# M149A.net
KiCad netlist of a schematic drawn in EAGLE
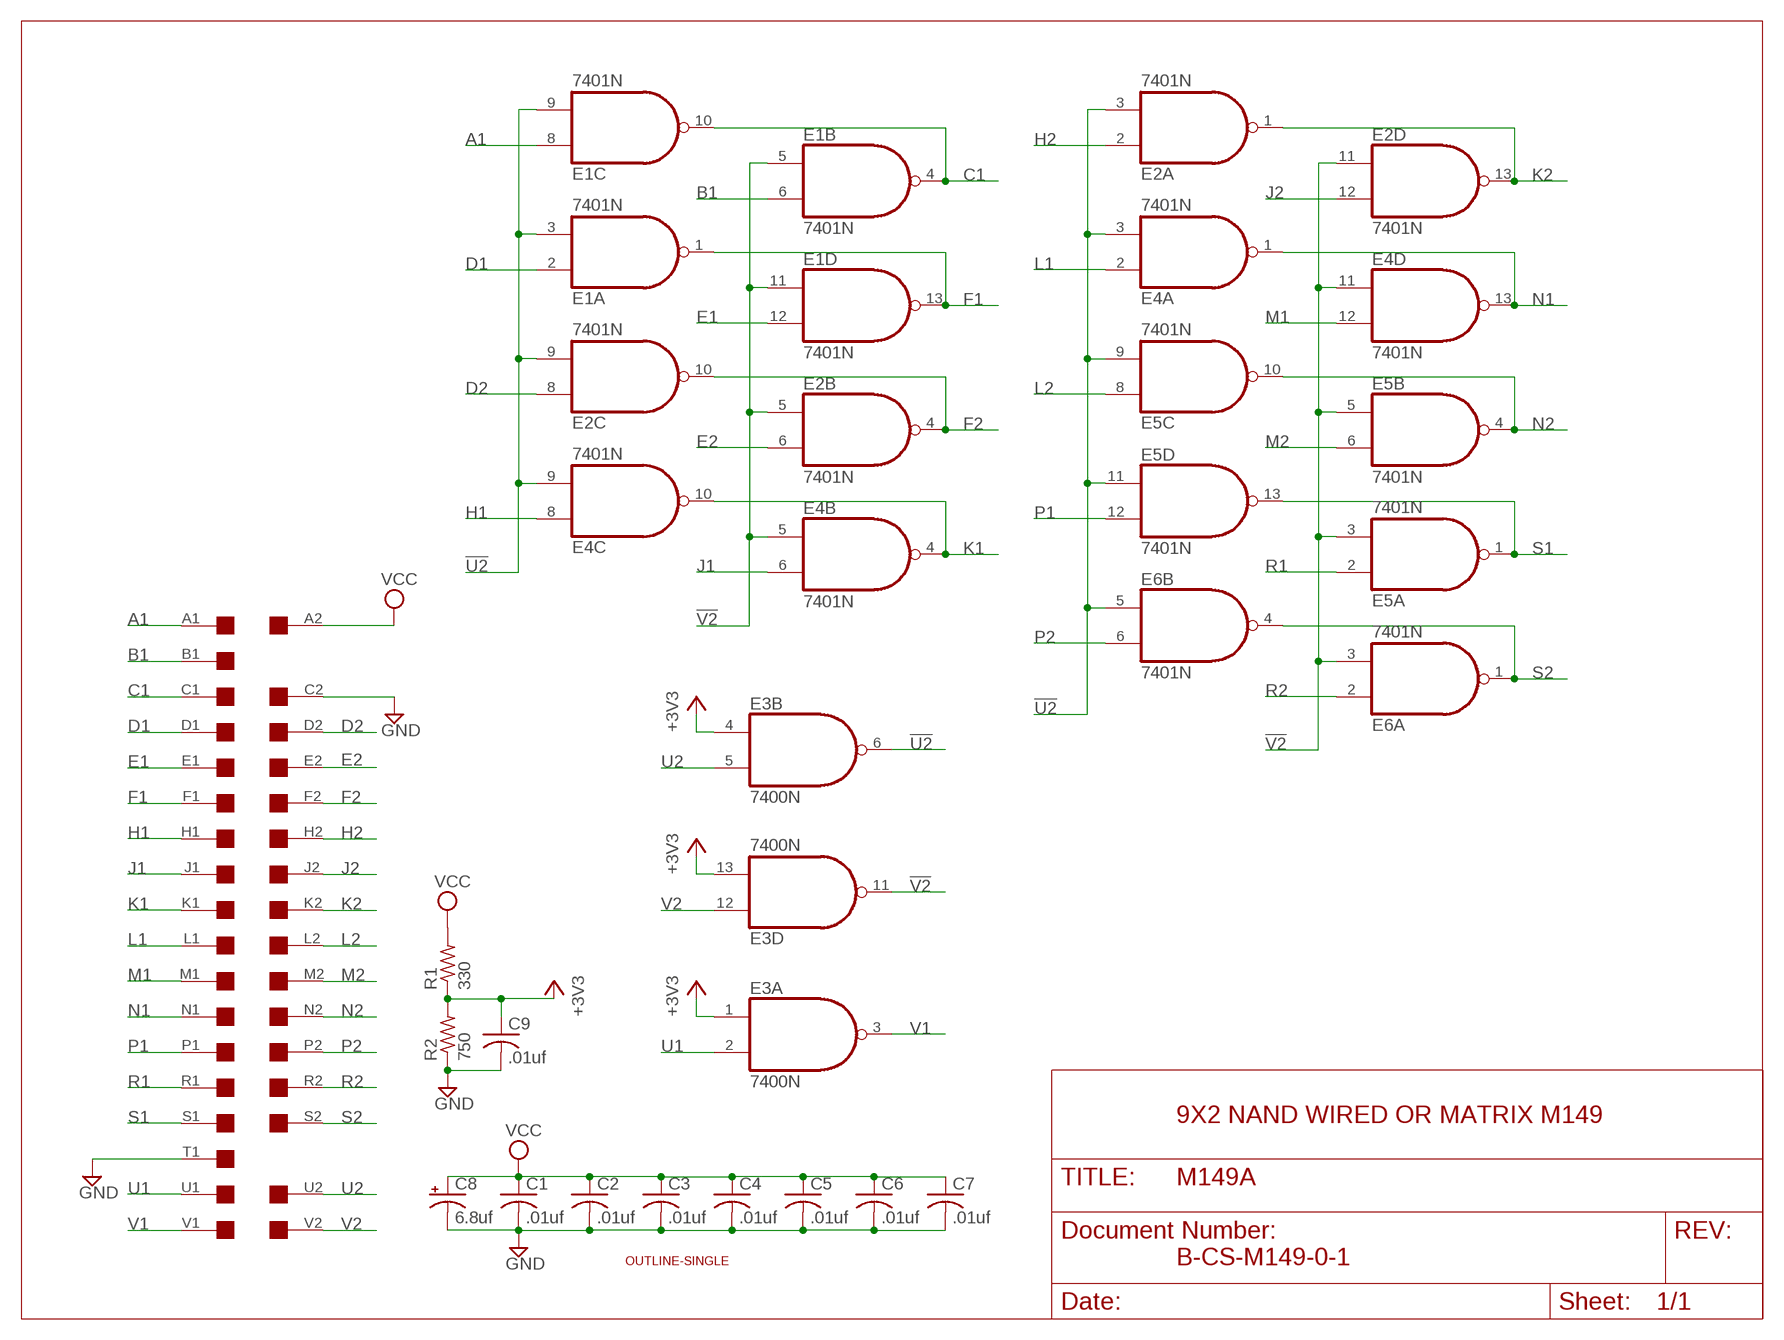
[diagram p0: schematic, sheet 1]

(export (version "E")
  (design (tool "Eeschema 10.0.6"))
  (components
    (comp (ref "C1")
      (value ".01uf")
      (footprint "eagle-import:C050-025X075")
      (libsource (lib "eagle-import") (part "C-US050-025X075"))
    )
    (comp (ref "C2")
      (value ".01uf")
      (footprint "eagle-import:C050-025X075")
      (libsource (lib "eagle-import") (part "C-US050-025X075"))
    )
    (comp (ref "C3")
      (value ".01uf")
      (footprint "eagle-import:C050-025X075")
      (libsource (lib "eagle-import") (part "C-US050-025X075"))
    )
    (comp (ref "C4")
      (value ".01uf")
      (footprint "eagle-import:C050-025X075")
      (libsource (lib "eagle-import") (part "C-US050-025X075"))
    )
    (comp (ref "C5")
      (value ".01uf")
      (footprint "eagle-import:C050-025X075")
      (libsource (lib "eagle-import") (part "C-US050-025X075"))
    )
    (comp (ref "C6")
      (value ".01uf")
      (footprint "eagle-import:C050-025X075")
      (libsource (lib "eagle-import") (part "C-US050-025X075"))
    )
    (comp (ref "C7")
      (value ".01uf")
      (footprint "eagle-import:C050-025X075")
      (libsource (lib "eagle-import") (part "C-US050-025X075"))
    )
    (comp (ref "C8")
      (value "6.8uf")
      (footprint "eagle-import:E15-5")
      (libsource (lib "eagle-import") (part "CPOL-USE15-5AXIAL"))
    )
    (comp (ref "C9")
      (value ".01uf")
      (footprint "eagle-import:C050-025X075")
      (libsource (lib "eagle-import") (part "C-US050-025X075"))
    )
    (comp (ref "E1")
      (value "7401N")
      (footprint "eagle-import:DIL14")
      (libsource (lib "eagle-import") (part "7401NLS"))
    )
    (comp (ref "E2")
      (value "7401N")
      (footprint "eagle-import:DIL14")
      (libsource (lib "eagle-import") (part "7401NLS"))
    )
    (comp (ref "E3")
      (value "7400N")
      (footprint "eagle-import:DIL14")
      (libsource (lib "eagle-import") (part "7400N"))
    )
    (comp (ref "E4")
      (value "7401N")
      (footprint "eagle-import:DIL14")
      (libsource (lib "eagle-import") (part "7401NLS"))
    )
    (comp (ref "E5")
      (value "7401N")
      (footprint "eagle-import:DIL14")
      (libsource (lib "eagle-import") (part "7401NLS"))
    )
    (comp (ref "E6")
      (value "7401N")
      (footprint "eagle-import:DIL14")
      (libsource (lib "eagle-import") (part "7401NLS"))
    )
    (comp (ref "R1")
      (value "330")
      (footprint "eagle-import:0207_10")
      (libsource (lib "eagle-import") (part "R-US_0207/10"))
    )
    (comp (ref "R2")
      (value "750")
      (footprint "eagle-import:0207_10")
      (libsource (lib "eagle-import") (part "R-US_0207/10"))
    )
    (comp (ref "U$1")
      (value "SINGLE")
      (footprint "eagle-import:EDGE-CON2")
      (libsource (lib "eagle-import") (part "SINGLE"))
    )
    (comp (ref "U$4")
      (value "OUTLINE-SINGLE")
      (footprint "eagle-import:SINGLE")
      (libsource (lib "eagle-import") (part "OUTLINE-SINGLE"))
    )
  )
  (nets
    (net (code "1") (name "+3V3") (class "Default")
      (node (ref "C9") (pin "1") (pinfunction "1_1") (pintype "passive"))
      (node (ref "E3") (pin "1") (pinfunction "I0_1") (pintype "input"))
      (node (ref "E3") (pin "13") (pinfunction "I1_13") (pintype "input"))
      (node (ref "E3") (pin "4") (pinfunction "I0_4") (pintype "input"))
      (node (ref "R1") (pin "1") (pinfunction "1_1") (pintype "passive"))
      (node (ref "R2") (pin "2") (pinfunction "2_2") (pintype "passive"))
    )
    (net (code "2") (name "/A1") (class "Default")
      (node (ref "E1") (pin "8") (pinfunction "I0_8") (pintype "input"))
      (node (ref "U$1") (pin "A1") (pinfunction "1_A1") (pintype "bidirectional"))
    )
    (net (code "3") (name "/B1") (class "Default")
      (node (ref "E1") (pin "6") (pinfunction "I1_6") (pintype "input"))
      (node (ref "U$1") (pin "B1") (pinfunction "1_B1") (pintype "bidirectional"))
    )
    (net (code "4") (name "/C1") (class "Default")
      (node (ref "E1") (pin "10") (pinfunction "O_10") (pintype "open_collector"))
      (node (ref "E1") (pin "4") (pinfunction "O_4") (pintype "open_collector"))
      (node (ref "U$1") (pin "C1") (pinfunction "1_C1") (pintype "bidirectional"))
    )
    (net (code "5") (name "/D1") (class "Default")
      (node (ref "E1") (pin "2") (pinfunction "I0_2") (pintype "input"))
      (node (ref "U$1") (pin "D1") (pinfunction "1_D1") (pintype "bidirectional"))
    )
    (net (code "6") (name "/D2") (class "Default")
      (node (ref "E2") (pin "8") (pinfunction "I0_8") (pintype "input"))
      (node (ref "U$1") (pin "D2") (pinfunction "1_D2") (pintype "bidirectional"))
    )
    (net (code "7") (name "/E1") (class "Default")
      (node (ref "E1") (pin "12") (pinfunction "I1_12") (pintype "input"))
      (node (ref "U$1") (pin "E1") (pinfunction "1_E1") (pintype "bidirectional"))
    )
    (net (code "8") (name "/E2") (class "Default")
      (node (ref "E2") (pin "6") (pinfunction "I1_6") (pintype "input"))
      (node (ref "U$1") (pin "E2") (pinfunction "1_E2") (pintype "bidirectional"))
    )
    (net (code "9") (name "/F1") (class "Default")
      (node (ref "E1") (pin "1") (pinfunction "O_1") (pintype "open_collector"))
      (node (ref "E1") (pin "13") (pinfunction "O_13") (pintype "open_collector"))
      (node (ref "U$1") (pin "F1") (pinfunction "1_F1") (pintype "bidirectional"))
    )
    (net (code "10") (name "/F2") (class "Default")
      (node (ref "E2") (pin "10") (pinfunction "O_10") (pintype "open_collector"))
      (node (ref "E2") (pin "4") (pinfunction "O_4") (pintype "open_collector"))
      (node (ref "U$1") (pin "F2") (pinfunction "1_F2") (pintype "bidirectional"))
    )
    (net (code "11") (name "/H1") (class "Default")
      (node (ref "E4") (pin "8") (pinfunction "I0_8") (pintype "input"))
      (node (ref "U$1") (pin "H1") (pinfunction "1_H1") (pintype "bidirectional"))
    )
    (net (code "12") (name "/H2") (class "Default")
      (node (ref "E2") (pin "2") (pinfunction "I0_2") (pintype "input"))
      (node (ref "U$1") (pin "H2") (pinfunction "1_H2") (pintype "bidirectional"))
    )
    (net (code "13") (name "/J1") (class "Default")
      (node (ref "E4") (pin "6") (pinfunction "I1_6") (pintype "input"))
      (node (ref "U$1") (pin "J1") (pinfunction "1_J1") (pintype "bidirectional"))
    )
    (net (code "14") (name "/J2") (class "Default")
      (node (ref "E2") (pin "12") (pinfunction "I1_12") (pintype "input"))
      (node (ref "U$1") (pin "J2") (pinfunction "1_J2") (pintype "bidirectional"))
    )
    (net (code "15") (name "/K1") (class "Default")
      (node (ref "E4") (pin "10") (pinfunction "O_10") (pintype "open_collector"))
      (node (ref "E4") (pin "4") (pinfunction "O_4") (pintype "open_collector"))
      (node (ref "U$1") (pin "K1") (pinfunction "1_K1") (pintype "bidirectional"))
    )
    (net (code "16") (name "/K2") (class "Default")
      (node (ref "E2") (pin "1") (pinfunction "O_1") (pintype "open_collector"))
      (node (ref "E2") (pin "13") (pinfunction "O_13") (pintype "open_collector"))
      (node (ref "U$1") (pin "K2") (pinfunction "1_K2") (pintype "bidirectional"))
    )
    (net (code "17") (name "/L1") (class "Default")
      (node (ref "E4") (pin "2") (pinfunction "I0_2") (pintype "input"))
      (node (ref "U$1") (pin "L1") (pinfunction "1_L1") (pintype "bidirectional"))
    )
    (net (code "18") (name "/L2") (class "Default")
      (node (ref "E5") (pin "8") (pinfunction "I0_8") (pintype "input"))
      (node (ref "U$1") (pin "L2") (pinfunction "1_L2") (pintype "bidirectional"))
    )
    (net (code "19") (name "/M1") (class "Default")
      (node (ref "E4") (pin "12") (pinfunction "I1_12") (pintype "input"))
      (node (ref "U$1") (pin "M1") (pinfunction "1_M1") (pintype "bidirectional"))
    )
    (net (code "20") (name "/M2") (class "Default")
      (node (ref "E5") (pin "6") (pinfunction "I1_6") (pintype "input"))
      (node (ref "U$1") (pin "M2") (pinfunction "1_M2") (pintype "bidirectional"))
    )
    (net (code "21") (name "/N1") (class "Default")
      (node (ref "E4") (pin "1") (pinfunction "O_1") (pintype "open_collector"))
      (node (ref "E4") (pin "13") (pinfunction "O_13") (pintype "open_collector"))
      (node (ref "U$1") (pin "N1") (pinfunction "1_N1") (pintype "bidirectional"))
    )
    (net (code "22") (name "/N2") (class "Default")
      (node (ref "E5") (pin "10") (pinfunction "O_10") (pintype "open_collector"))
      (node (ref "E5") (pin "4") (pinfunction "O_4") (pintype "open_collector"))
      (node (ref "U$1") (pin "N2") (pinfunction "1_N2") (pintype "bidirectional"))
    )
    (net (code "23") (name "/P1") (class "Default")
      (node (ref "E5") (pin "12") (pinfunction "I1_12") (pintype "input"))
      (node (ref "U$1") (pin "P1") (pinfunction "1_P1") (pintype "bidirectional"))
    )
    (net (code "24") (name "/P2") (class "Default")
      (node (ref "E6") (pin "6") (pinfunction "I1_6") (pintype "input"))
      (node (ref "U$1") (pin "P2") (pinfunction "1_P2") (pintype "bidirectional"))
    )
    (net (code "25") (name "/R1") (class "Default")
      (node (ref "E5") (pin "2") (pinfunction "I0_2") (pintype "input"))
      (node (ref "U$1") (pin "R1") (pinfunction "1_R1") (pintype "bidirectional"))
    )
    (net (code "26") (name "/R2") (class "Default")
      (node (ref "E6") (pin "2") (pinfunction "I0_2") (pintype "input"))
      (node (ref "U$1") (pin "R2") (pinfunction "1_R2") (pintype "bidirectional"))
    )
    (net (code "27") (name "/S1") (class "Default")
      (node (ref "E5") (pin "1") (pinfunction "O_1") (pintype "open_collector"))
      (node (ref "E5") (pin "13") (pinfunction "O_13") (pintype "open_collector"))
      (node (ref "U$1") (pin "S1") (pinfunction "1_S1") (pintype "bidirectional"))
    )
    (net (code "28") (name "/S2") (class "Default")
      (node (ref "E6") (pin "1") (pinfunction "O_1") (pintype "open_collector"))
      (node (ref "E6") (pin "4") (pinfunction "O_4") (pintype "open_collector"))
      (node (ref "U$1") (pin "S2") (pinfunction "1_S2") (pintype "bidirectional"))
    )
    (net (code "29") (name "/U1") (class "Default")
      (node (ref "E3") (pin "2") (pinfunction "I1_2") (pintype "input"))
      (node (ref "U$1") (pin "U1") (pinfunction "1_U1") (pintype "bidirectional"))
    )
    (net (code "30") (name "/U2") (class "Default")
      (node (ref "E3") (pin "5") (pinfunction "I1_5") (pintype "input"))
      (node (ref "U$1") (pin "U2") (pinfunction "1_U2") (pintype "bidirectional"))
    )
    (net (code "31") (name "/V1") (class "Default")
      (node (ref "E3") (pin "3") (pinfunction "O_3") (pintype "output"))
      (node (ref "U$1") (pin "V1") (pinfunction "1_V1") (pintype "bidirectional"))
    )
    (net (code "32") (name "/V2") (class "Default")
      (node (ref "E3") (pin "12") (pinfunction "I0_12") (pintype "input"))
      (node (ref "U$1") (pin "V2") (pinfunction "1_V2") (pintype "bidirectional"))
    )
    (net (code "33") (name "/~{U2}") (class "Default")
      (node (ref "E1") (pin "3") (pinfunction "I1_3") (pintype "input"))
      (node (ref "E1") (pin "9") (pinfunction "I1_9") (pintype "input"))
      (node (ref "E2") (pin "3") (pinfunction "I1_3") (pintype "input"))
      (node (ref "E2") (pin "9") (pinfunction "I1_9") (pintype "input"))
      (node (ref "E3") (pin "6") (pinfunction "O_6") (pintype "output"))
      (node (ref "E4") (pin "3") (pinfunction "I1_3") (pintype "input"))
      (node (ref "E4") (pin "9") (pinfunction "I1_9") (pintype "input"))
      (node (ref "E5") (pin "11") (pinfunction "I0_11") (pintype "input"))
      (node (ref "E5") (pin "9") (pinfunction "I1_9") (pintype "input"))
      (node (ref "E6") (pin "5") (pinfunction "I0_5") (pintype "input"))
    )
    (net (code "34") (name "/~{V2}") (class "Default")
      (node (ref "E1") (pin "11") (pinfunction "I0_11") (pintype "input"))
      (node (ref "E1") (pin "5") (pinfunction "I0_5") (pintype "input"))
      (node (ref "E2") (pin "11") (pinfunction "I0_11") (pintype "input"))
      (node (ref "E2") (pin "5") (pinfunction "I0_5") (pintype "input"))
      (node (ref "E3") (pin "11") (pinfunction "O_11") (pintype "output"))
      (node (ref "E4") (pin "11") (pinfunction "I0_11") (pintype "input"))
      (node (ref "E4") (pin "5") (pinfunction "I0_5") (pintype "input"))
      (node (ref "E5") (pin "3") (pinfunction "I1_3") (pintype "input"))
      (node (ref "E5") (pin "5") (pinfunction "I0_5") (pintype "input"))
      (node (ref "E6") (pin "3") (pinfunction "I1_3") (pintype "input"))
    )
    (net (code "35") (name "GND") (class "Default")
      (node (ref "C1") (pin "2") (pinfunction "2_2") (pintype "passive"))
      (node (ref "C2") (pin "2") (pinfunction "2_2") (pintype "passive"))
      (node (ref "C3") (pin "2") (pinfunction "2_2") (pintype "passive"))
      (node (ref "C4") (pin "2") (pinfunction "2_2") (pintype "passive"))
      (node (ref "C5") (pin "2") (pinfunction "2_2") (pintype "passive"))
      (node (ref "C6") (pin "2") (pinfunction "2_2") (pintype "passive"))
      (node (ref "C7") (pin "2") (pinfunction "2_2") (pintype "passive"))
      (node (ref "C8") (pin "-") (pinfunction "-_-") (pintype "passive"))
      (node (ref "C9") (pin "2") (pinfunction "2_2") (pintype "passive"))
      (node (ref "R2") (pin "1") (pinfunction "1_1") (pintype "passive"))
      (node (ref "U$1") (pin "C2") (pinfunction "1_C2") (pintype "bidirectional"))
      (node (ref "U$1") (pin "T1") (pinfunction "1_T1") (pintype "bidirectional"))
    )
    (net (code "36") (name "VCC") (class "Default")
      (node (ref "C1") (pin "1") (pinfunction "1_1") (pintype "passive"))
      (node (ref "C2") (pin "1") (pinfunction "1_1") (pintype "passive"))
      (node (ref "C3") (pin "1") (pinfunction "1_1") (pintype "passive"))
      (node (ref "C4") (pin "1") (pinfunction "1_1") (pintype "passive"))
      (node (ref "C5") (pin "1") (pinfunction "1_1") (pintype "passive"))
      (node (ref "C6") (pin "1") (pinfunction "1_1") (pintype "passive"))
      (node (ref "C7") (pin "1") (pinfunction "1_1") (pintype "passive"))
      (node (ref "C8") (pin "+") (pinfunction "+_+") (pintype "passive"))
      (node (ref "R1") (pin "2") (pinfunction "2_2") (pintype "passive"))
      (node (ref "U$1") (pin "A2") (pinfunction "1_A2") (pintype "bidirectional"))
    )
  )
)
